# 06_EEPROM.net
KiCad netlist of a schematic drawn in Altium Designer
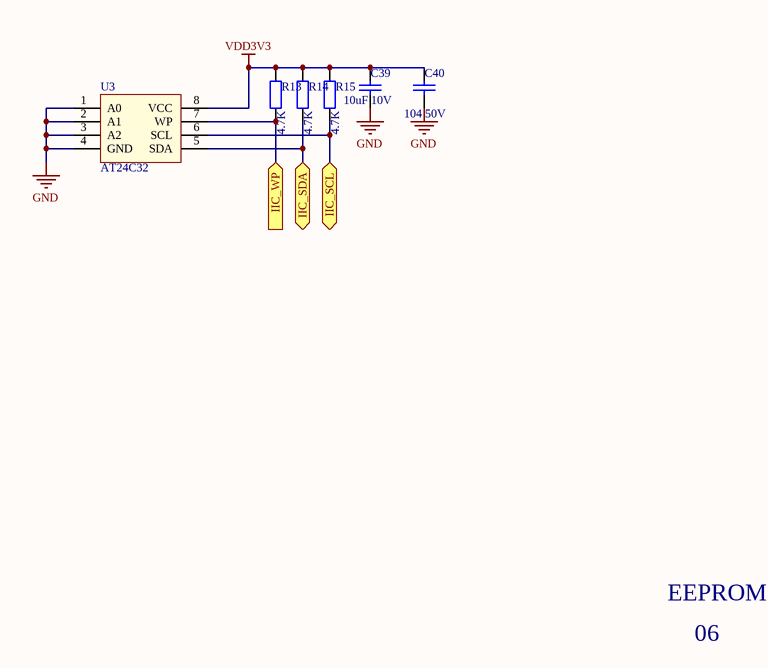
[diagram p0: 06_EEPROM.SchDoc]

(export (version "E")
  (design (tool "Eeschema 10.0.6"))
  (components
    (comp (ref "C39")
      (value "10uF 10V")
      (footprint "SMD-0603C")
      (description "贴片电容 20%")
      (libsource (lib "XiaoyI") (part "CAP4"))
    )
    (comp (ref "C40")
      (value "104 50V")
      (footprint "SMD-0603C")
      (description "贴片电容 20%")
      (libsource (lib "XiaoyI") (part "CAP4"))
    )
    (comp (ref "R13")
      (value "4.7K")
      (footprint "SMD-0603")
      (description "贴片电阻 5%")
      (libsource (lib "XiaoyI") (part "RES2"))
    )
    (comp (ref "R14")
      (value "4.7K")
      (footprint "SMD-0603")
      (description "贴片电阻 5%")
      (libsource (lib "XiaoyI") (part "RES2"))
    )
    (comp (ref "R15")
      (value "4.7K")
      (footprint "SMD-0603")
      (description "贴片电阻 5%")
      (libsource (lib "XiaoyI") (part "RES2"))
    )
    (comp (ref "U3")
      (value "AT24C32")
      (footprint "SOIC-8")
      (description "EEPROM")
      (libsource (lib "XiaoyI") (part "EEPROM"))
    )
  )
  (nets
    (net (code "1") (name "/IIC_SCL") (class "Default")
      (node (ref "R15") (pin "2") (pinfunction "2_2") (pintype "passive"))
      (node (ref "U3") (pin "6") (pinfunction "SCL_6") (pintype "passive"))
    )
    (net (code "2") (name "/IIC_SDA") (class "Default")
      (node (ref "R14") (pin "2") (pinfunction "2_2") (pintype "passive"))
      (node (ref "U3") (pin "5") (pinfunction "SDA_5") (pintype "passive"))
    )
    (net (code "3") (name "/IIC_WP") (class "Default")
      (node (ref "R13") (pin "2") (pinfunction "2_2") (pintype "passive"))
      (node (ref "U3") (pin "7") (pinfunction "WP_7") (pintype "passive"))
    )
    (net (code "4") (name "GND") (class "Default")
      (node (ref "C39") (pin "1") (pinfunction "1_1") (pintype "passive"))
      (node (ref "C40") (pin "1") (pinfunction "1_1") (pintype "passive"))
      (node (ref "U3") (pin "1") (pinfunction "A0_1") (pintype "passive"))
      (node (ref "U3") (pin "2") (pinfunction "A1_2") (pintype "passive"))
      (node (ref "U3") (pin "3") (pinfunction "A2_3") (pintype "passive"))
      (node (ref "U3") (pin "4") (pinfunction "GND_4") (pintype "passive"))
    )
    (net (code "5") (name "VDD3V3") (class "Default")
      (node (ref "C39") (pin "2") (pinfunction "2_2") (pintype "passive"))
      (node (ref "C40") (pin "2") (pinfunction "2_2") (pintype "passive"))
      (node (ref "R13") (pin "1") (pinfunction "1_1") (pintype "passive"))
      (node (ref "R14") (pin "1") (pinfunction "1_1") (pintype "passive"))
      (node (ref "R15") (pin "1") (pinfunction "1_1") (pintype "passive"))
      (node (ref "U3") (pin "8") (pinfunction "VCC_8") (pintype "passive"))
    )
  )
)
